# orienteringsklokke.net
KiCad netlist of a schematic drawn in EAGLE
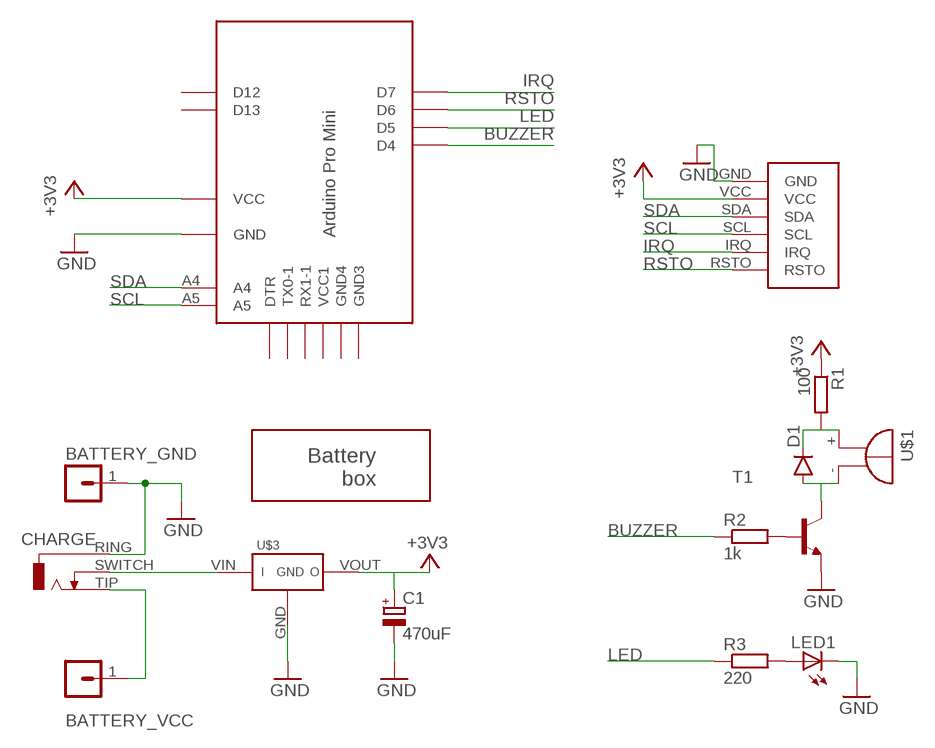
[diagram p0: schematic, sheet 1]

(export (version "E")
  (design (tool "Eeschema 10.0.6"))
  (components
    (comp (ref "BATTERY_GND")
      (value "MA01-1JC")
      (footprint "eagle-import:MA01-1J")
      (libsource (lib "eagle-import") (part "MA01-1JC"))
    )
    (comp (ref "BATTERY_VCC")
      (value "MA01-1JC")
      (footprint "eagle-import:MA01-1J")
      (libsource (lib "eagle-import") (part "MA01-1JC"))
    )
    (comp (ref "C1")
      (value "470uF")
      (footprint "eagle-import:E2,5-6")
      (libsource (lib "eagle-import") (part "CPOL-EUE2.5-6"))
    )
    (comp (ref "CHARGE")
      (value "ST613-JACK")
      (footprint "eagle-import:ST613-JACK")
      (libsource (lib "eagle-import") (part "ST613-JACK"))
    )
    (comp (ref "D1")
      (value "1N4148DOJ35-5")
      (footprint "eagle-import:DO35-5J")
      (libsource (lib "eagle-import") (part "1N4148DOJ35-5"))
    )
    (comp (ref "LED1")
      (value "LED3MM")
      (footprint "eagle-import:LED3MM")
      (libsource (lib "eagle-import") (part "LED3MM"))
    )
    (comp (ref "R1")
      (value "100")
      (footprint "eagle-import:0207_7")
      (libsource (lib "eagle-import") (part "R-EU_0207/7"))
    )
    (comp (ref "R2")
      (value "1k")
      (footprint "eagle-import:0207_7")
      (libsource (lib "eagle-import") (part "R-EU_0207/7"))
    )
    (comp (ref "R3")
      (value "220")
      (footprint "eagle-import:0207_7")
      (libsource (lib "eagle-import") (part "R-EU_0207/7"))
    )
    (comp (ref "T1")
      (value "2N3904-NPN-TO92-EBC")
      (footprint "eagle-import:TO92-EBC")
      (libsource (lib "eagle-import") (part "-NPN-TO92-EBC2N3904"))
    )
    (comp (ref "U$1")
      (value "BUZZER_J")
      (footprint "eagle-import:BUZZER_J")
      (libsource (lib "eagle-import") (part "BUZZER_J"))
    )
    (comp (ref "U$2")
      (value "NFC_MODULE_V3_I2C")
      (footprint "eagle-import:NFC_MODULE_V3_I2C")
      (libsource (lib "eagle-import") (part "NFC_MODULE_V3_I2C"))
    )
    (comp (ref "U$3")
      (value "VOLT_BOOST")
      (footprint "eagle-import:VOLT-BOOST")
      (libsource (lib "eagle-import") (part "VOLT_BOOST"))
    )
    (comp (ref "U$4")
      (value "ARD-PRO-MINI-ORIENTERING")
      (footprint "eagle-import:ARD_PRO_MINI_ORIENTERING")
      (libsource (lib "eagle-import") (part "ARD-PRO-MINI-ORIENTERING"))
    )
    (comp (ref "U$5")
      (value "BATTERY-BOX")
      (footprint "eagle-import:AAA-BATTERY-BOX-SINGLE")
      (libsource (lib "eagle-import") (part "BATTERY-BOX"))
    )
  )
  (nets
    (net (code "1") (name "+3V3") (class "Default")
      (node (ref "C1") (pin "+") (pinfunction "+_+") (pintype "passive"))
      (node (ref "R1") (pin "1") (pinfunction "1_1") (pintype "passive"))
      (node (ref "U$2") (pin "VCC") (pinfunction "VCC_VCC") (pintype "bidirectional"))
      (node (ref "U$3") (pin "VOUT") (pinfunction "VOUT_VOUT") (pintype "bidirectional"))
      (node (ref "U$4") (pin "VCC") (pinfunction "VCC_VCC") (pintype "bidirectional"))
    )
    (net (code "2") (name "BUZZER") (class "Default")
      (node (ref "R2") (pin "1") (pinfunction "1_1") (pintype "passive"))
      (node (ref "U$4") (pin "D4") (pinfunction "D4_D4") (pintype "bidirectional"))
    )
    (net (code "3") (name "GND") (class "Default")
      (node (ref "BATTERY_GND") (pin "1") (pinfunction "1_1") (pintype "passive"))
      (node (ref "C1") (pin "-") (pinfunction "-_-") (pintype "passive"))
      (node (ref "CHARGE") (pin "RING") (pinfunction "1_RING") (pintype "passive"))
      (node (ref "LED1") (pin "K") (pinfunction "C_K") (pintype "passive"))
      (node (ref "T1") (pin "E") (pinfunction "E_E") (pintype "passive"))
      (node (ref "U$2") (pin "GND") (pinfunction "GND_GND") (pintype "bidirectional"))
      (node (ref "U$3") (pin "GND") (pinfunction "GND_GND") (pintype "bidirectional"))
      (node (ref "U$4") (pin "GND") (pinfunction "GND_GND") (pintype "bidirectional"))
    )
    (net (code "4") (name "IRQ") (class "Default")
      (node (ref "U$2") (pin "IRQ") (pinfunction "IRQ_IRQ") (pintype "bidirectional"))
      (node (ref "U$4") (pin "D7") (pinfunction "D7_D7") (pintype "bidirectional"))
    )
    (net (code "5") (name "LED") (class "Default")
      (node (ref "R3") (pin "1") (pinfunction "1_1") (pintype "passive"))
      (node (ref "U$4") (pin "D5") (pinfunction "D5_D5") (pintype "bidirectional"))
    )
    (net (code "6") (name "Net-(CHARGE-2)") (class "Default")
      (node (ref "CHARGE") (pin "SWITCH") (pinfunction "2_SWITCH") (pintype "passive"))
      (node (ref "U$3") (pin "VIN") (pinfunction "VIN_VIN") (pintype "bidirectional"))
    )
    (net (code "7") (name "Net-(CHARGE-3)") (class "Default")
      (node (ref "BATTERY_VCC") (pin "1") (pinfunction "1_1") (pintype "passive"))
      (node (ref "CHARGE") (pin "TIP") (pinfunction "3_TIP") (pintype "passive"))
    )
    (net (code "8") (name "Net-(D1-PadA)") (class "Default")
      (node (ref "D1") (pin "A") (pinfunction "A_A") (pintype "passive"))
      (node (ref "T1") (pin "C") (pinfunction "C_C") (pintype "passive"))
      (node (ref "U$1") (pin "-") (pinfunction "-_-") (pintype "passive"))
    )
    (net (code "9") (name "Net-(D1-PadC)") (class "Default")
      (node (ref "D1") (pin "C") (pinfunction "C_C") (pintype "passive"))
      (node (ref "R1") (pin "2") (pinfunction "2_2") (pintype "passive"))
      (node (ref "U$1") (pin "+") (pinfunction "+_+") (pintype "passive"))
    )
    (net (code "10") (name "Net-(LED1-PadA)") (class "Default")
      (node (ref "LED1") (pin "A") (pinfunction "A_A") (pintype "passive"))
      (node (ref "R3") (pin "2") (pinfunction "2_2") (pintype "passive"))
    )
    (net (code "11") (name "Net-(R2-Pad2)") (class "Default")
      (node (ref "R2") (pin "2") (pinfunction "2_2") (pintype "passive"))
      (node (ref "T1") (pin "B") (pinfunction "B_B") (pintype "passive"))
    )
    (net (code "12") (name "RSTO") (class "Default")
      (node (ref "U$2") (pin "RSTO") (pinfunction "RSTO_RSTO") (pintype "bidirectional"))
      (node (ref "U$4") (pin "D6") (pinfunction "D6_D6") (pintype "bidirectional"))
    )
    (net (code "13") (name "SCL") (class "Default")
      (node (ref "U$2") (pin "SCL") (pinfunction "SCL_SCL") (pintype "bidirectional"))
      (node (ref "U$4") (pin "A5") (pinfunction "A5_A5") (pintype "bidirectional"))
    )
    (net (code "14") (name "SDA") (class "Default")
      (node (ref "U$2") (pin "SDA") (pinfunction "SDA_SDA") (pintype "bidirectional"))
      (node (ref "U$4") (pin "A4") (pinfunction "A4_A4") (pintype "bidirectional"))
    )
    (net (code "15") (name "unconnected-(U$4-GND3-PadGND2)") (class "Default")
      (node (ref "U$4") (pin "GND2") (pinfunction "GND3_GND2") (pintype "bidirectional"))
    )
    (net (code "16") (name "unconnected-(U$4-GND4-PadGND3)") (class "Default")
      (node (ref "U$4") (pin "GND3") (pinfunction "GND4_GND3") (pintype "bidirectional"))
    )
    (net (code "17") (name "unconnected-(U$4-PadD12)") (class "Default")
      (node (ref "U$4") (pin "D12") (pinfunction "D12_D12") (pintype "bidirectional"))
    )
    (net (code "18") (name "unconnected-(U$4-PadD13)") (class "Default")
      (node (ref "U$4") (pin "D13") (pinfunction "D13_D13") (pintype "bidirectional"))
    )
    (net (code "19") (name "unconnected-(U$4-PadDTR)") (class "Default")
      (node (ref "U$4") (pin "DTR") (pinfunction "DTR_DTR") (pintype "bidirectional"))
    )
    (net (code "20") (name "unconnected-(U$4-PadRX1-1)") (class "Default")
      (node (ref "U$4") (pin "RX1-1") (pinfunction "RX1-1_RX1-1") (pintype "bidirectional"))
    )
    (net (code "21") (name "unconnected-(U$4-PadTX0-1)") (class "Default")
      (node (ref "U$4") (pin "TX0-1") (pinfunction "TX0-1_TX0-1") (pintype "bidirectional"))
    )
    (net (code "22") (name "unconnected-(U$4-PadVCC1)") (class "Default")
      (node (ref "U$4") (pin "VCC1") (pinfunction "VCC1_VCC1") (pintype "bidirectional"))
    )
  )
)
